# AS5048_Encoder.net
KiCad netlist of a schematic drawn in EAGLE
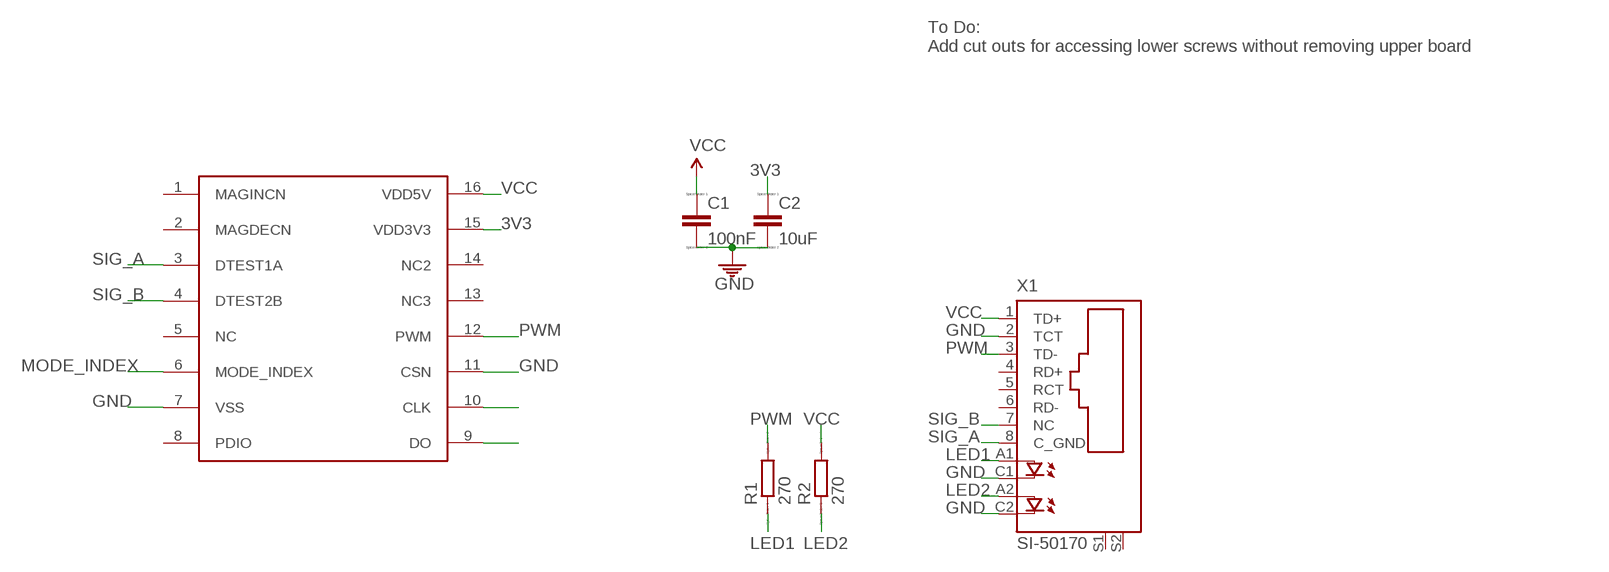
[diagram p0: schematic, sheet 1]

(export (version "E")
  (design (tool "Eeschema 10.0.6"))
  (components
    (comp (ref "C1")
      (value "100nF")
      (footprint "eagle-import:C0805")
      (libsource (lib "eagle-import") (part "C"))
    )
    (comp (ref "C2")
      (value "10uF")
      (footprint "eagle-import:C0805")
      (libsource (lib "eagle-import") (part "C"))
    )
    (comp (ref "R1")
      (value "270")
      (footprint "eagle-import:R0805")
      (libsource (lib "eagle-import") (part "R"))
    )
    (comp (ref "R2")
      (value "270")
      (footprint "eagle-import:R0805")
      (libsource (lib "eagle-import") (part "R"))
    )
    (comp (ref "U$2")
      (value "AS5145")
      (footprint "eagle-import:SSOP16")
      (libsource (lib "eagle-import") (part "AS5145"))
    )
    (comp (ref "X1")
      (value "SI-50170")
      (footprint "eagle-import:SI-50170")
      (libsource (lib "eagle-import") (part "SI-50170"))
    )
  )
  (nets
    (net (code "1") (name "/3V3") (class "Default")
      (node (ref "C2") (pin "1") (pinfunction "1_1") (pintype "passive"))
      (node (ref "U$2") (pin "15") (pinfunction "VDD3V3_15") (pintype "bidirectional"))
    )
    (net (code "2") (name "/LED1") (class "Default")
      (node (ref "R1") (pin "1") (pinfunction "1_1") (pintype "passive"))
      (node (ref "X1") (pin "A1") (pinfunction "A_A1") (pintype "passive"))
    )
    (net (code "3") (name "/LED2") (class "Default")
      (node (ref "R2") (pin "1") (pinfunction "1_1") (pintype "passive"))
      (node (ref "X1") (pin "A2") (pinfunction "A1_A2") (pintype "passive"))
    )
    (net (code "4") (name "/MODE_INDEX") (class "Default")
      (node (ref "U$2") (pin "6") (pinfunction "MODE_INDEX_6") (pintype "bidirectional"))
    )
    (net (code "5") (name "/PWM") (class "Default")
      (node (ref "R1") (pin "2") (pinfunction "2_2") (pintype "passive"))
      (node (ref "U$2") (pin "12") (pinfunction "PWM_12") (pintype "bidirectional"))
      (node (ref "X1") (pin "3") (pinfunction "TD-_3") (pintype "passive"))
    )
    (net (code "6") (name "/SIG_A") (class "Default")
      (node (ref "U$2") (pin "3") (pinfunction "DTEST1A_3") (pintype "bidirectional"))
      (node (ref "X1") (pin "8") (pinfunction "C_GND_8") (pintype "passive"))
    )
    (net (code "7") (name "/SIG_B") (class "Default")
      (node (ref "U$2") (pin "4") (pinfunction "DTEST2B_4") (pintype "bidirectional"))
      (node (ref "X1") (pin "7") (pinfunction "NC_7") (pintype "passive"))
    )
    (net (code "8") (name "GND") (class "Default")
      (node (ref "C1") (pin "2") (pinfunction "2_2") (pintype "passive"))
      (node (ref "C2") (pin "2") (pinfunction "2_2") (pintype "passive"))
      (node (ref "U$2") (pin "11") (pinfunction "CSN_11") (pintype "bidirectional"))
      (node (ref "U$2") (pin "7") (pinfunction "VSS_7") (pintype "bidirectional"))
      (node (ref "X1") (pin "2") (pinfunction "TCT_2") (pintype "passive"))
      (node (ref "X1") (pin "C1") (pinfunction "C_C1") (pintype "passive"))
      (node (ref "X1") (pin "C2") (pinfunction "C1_C2") (pintype "passive"))
    )
    (net (code "9") (name "VCC") (class "Default")
      (node (ref "C1") (pin "1") (pinfunction "1_1") (pintype "passive"))
      (node (ref "R2") (pin "2") (pinfunction "2_2") (pintype "passive"))
      (node (ref "U$2") (pin "16") (pinfunction "VDD5V_16") (pintype "bidirectional"))
      (node (ref "X1") (pin "1") (pinfunction "TD+_1") (pintype "passive"))
    )
    (net (code "10") (name "unconnected-(U$2-CLK-Pad10)") (class "Default")
      (node (ref "U$2") (pin "10") (pinfunction "CLK_10") (pintype "bidirectional"))
    )
    (net (code "11") (name "unconnected-(U$2-DO-Pad9)") (class "Default")
      (node (ref "U$2") (pin "9") (pinfunction "DO_9") (pintype "bidirectional"))
    )
    (net (code "12") (name "unconnected-(U$2-MAGDECN-Pad2)") (class "Default")
      (node (ref "U$2") (pin "2") (pinfunction "MAGDECN_2") (pintype "bidirectional"))
    )
    (net (code "13") (name "unconnected-(U$2-MAGINCN-Pad1)") (class "Default")
      (node (ref "U$2") (pin "1") (pinfunction "MAGINCN_1") (pintype "bidirectional"))
    )
    (net (code "14") (name "unconnected-(U$2-NC-Pad5)") (class "Default")
      (node (ref "U$2") (pin "5") (pinfunction "NC_5") (pintype "bidirectional"))
    )
    (net (code "15") (name "unconnected-(U$2-NC2-Pad14)") (class "Default")
      (node (ref "U$2") (pin "14") (pinfunction "NC2_14") (pintype "bidirectional"))
    )
    (net (code "16") (name "unconnected-(U$2-NC3-Pad13)") (class "Default")
      (node (ref "U$2") (pin "13") (pinfunction "NC3_13") (pintype "bidirectional"))
    )
    (net (code "17") (name "unconnected-(U$2-PDIO-Pad8)") (class "Default")
      (node (ref "U$2") (pin "8") (pinfunction "PDIO_8") (pintype "bidirectional"))
    )
    (net (code "18") (name "unconnected-(X1-PadS1)") (class "Default")
      (node (ref "X1") (pin "S1") (pinfunction "S1_S1") (pintype "passive"))
    )
    (net (code "19") (name "unconnected-(X1-PadS2)") (class "Default")
      (node (ref "X1") (pin "S2") (pinfunction "S2_S2") (pintype "passive"))
    )
    (net (code "20") (name "unconnected-(X1-RCT-Pad5)") (class "Default")
      (node (ref "X1") (pin "5") (pinfunction "RCT_5") (pintype "passive"))
    )
    (net (code "21") (name "unconnected-(X1-RD+-Pad4)") (class "Default")
      (node (ref "X1") (pin "4") (pinfunction "RD+_4") (pintype "passive"))
    )
    (net (code "22") (name "unconnected-(X1-RD--Pad6)") (class "Default")
      (node (ref "X1") (pin "6") (pinfunction "RD-_6") (pintype "passive"))
    )
  )
)
